# BARRAMENTO.net
KiCad netlist of a schematic drawn in Altium Designer
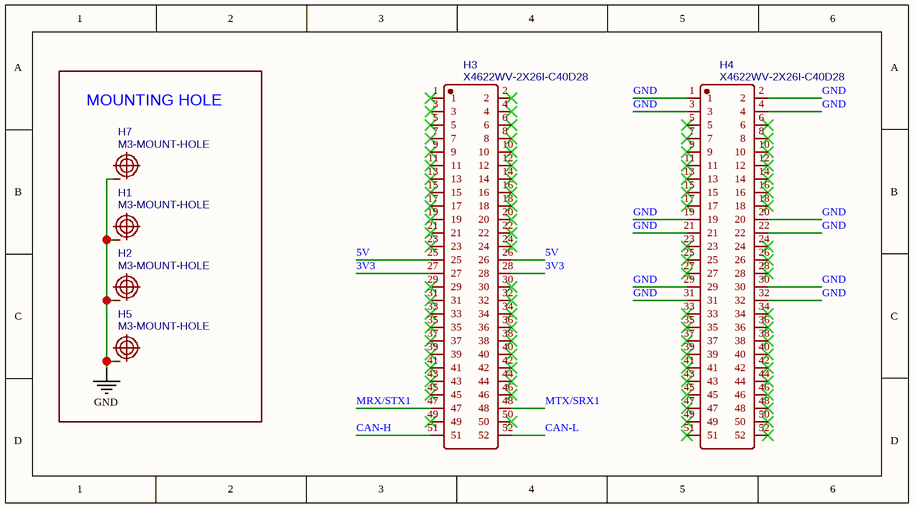
[diagram p0: BARRAMENTO.schdoc]

(export (version "E")
  (design (tool "Eeschema 10.0.6"))
  (components
    (comp (ref "H1")
      (value "M3-MOUNT-HOLE")
      (fields (field (name "CONTRIBUTOR") "amugona"))
      (libsource (lib "altium-import") (part "root_0_M3-MOUNT-HOLE_"))
    )
    (comp (ref "H2")
      (value "M3-MOUNT-HOLE")
      (fields (field (name "CONTRIBUTOR") "amugona"))
      (libsource (lib "altium-import") (part "root_0_M3-MOUNT-HOLE_"))
    )
    (comp (ref "H3")
      (value "X4622WV-2X26I-C40D28")
      (fields
        (field (name "BOM_SUPPLIER PART") "C2881769")
        (field (name "BOM_MANUFACTURER PART") "X1321FV-2x26-C43D24")
        (field (name "CONTRIBUTOR") "LCSC")
      )
      (libsource (lib "altium-import") (part "root_0_X4622WV-2X26I-C40D28_"))
    )
    (comp (ref "H4")
      (value "X4622WV-2X26I-C40D28")
      (fields
        (field (name "BOM_SUPPLIER PART") "C2881769")
        (field (name "BOM_MANUFACTURER PART") "X1321FV-2x26-C43D24")
        (field (name "CONTRIBUTOR") "LCSC")
      )
      (libsource (lib "altium-import") (part "root_0_X4622WV-2X26I-C40D28_"))
    )
    (comp (ref "H5")
      (value "M3-MOUNT-HOLE")
      (fields (field (name "CONTRIBUTOR") "amugona"))
      (libsource (lib "altium-import") (part "root_0_M3-MOUNT-HOLE_"))
    )
    (comp (ref "H7")
      (value "M3-MOUNT-HOLE")
      (fields (field (name "CONTRIBUTOR") "amugona"))
      (libsource (lib "altium-import") (part "root_0_M3-MOUNT-HOLE_"))
    )
  )
  (nets
    (net (code "1") (name "/3V3") (class "Default")
      (node (ref "H3") (pin "27") (pinfunction "27_27") (pintype "passive"))
      (node (ref "H3") (pin "28") (pinfunction "28_28") (pintype "passive"))
    )
    (net (code "2") (name "/5V") (class "Default")
      (node (ref "H3") (pin "25") (pinfunction "25_25") (pintype "passive"))
      (node (ref "H3") (pin "26") (pinfunction "26_26") (pintype "passive"))
    )
    (net (code "3") (name "/CAN-H") (class "Default")
      (node (ref "H3") (pin "51") (pinfunction "51_51") (pintype "passive"))
    )
    (net (code "4") (name "/CAN-L") (class "Default")
      (node (ref "H3") (pin "52") (pinfunction "52_52") (pintype "passive"))
    )
    (net (code "5") (name "/MRX{slash}STX1") (class "Default")
      (node (ref "H3") (pin "47") (pinfunction "47_47") (pintype "passive"))
    )
    (net (code "6") (name "/MTX{slash}SRX1") (class "Default")
      (node (ref "H3") (pin "48") (pinfunction "48_48") (pintype "passive"))
    )
    (net (code "7") (name "GND") (class "Default")
      (node (ref "H1") (pin "1") (pinfunction "1_1") (pintype "passive"))
      (node (ref "H2") (pin "1") (pinfunction "1_1") (pintype "passive"))
      (node (ref "H4") (pin "1") (pinfunction "1_1") (pintype "passive"))
      (node (ref "H4") (pin "19") (pinfunction "19_19") (pintype "passive"))
      (node (ref "H4") (pin "2") (pinfunction "2_2") (pintype "passive"))
      (node (ref "H4") (pin "20") (pinfunction "20_20") (pintype "passive"))
      (node (ref "H4") (pin "21") (pinfunction "21_21") (pintype "passive"))
      (node (ref "H4") (pin "22") (pinfunction "22_22") (pintype "passive"))
      (node (ref "H4") (pin "29") (pinfunction "29_29") (pintype "passive"))
      (node (ref "H4") (pin "3") (pinfunction "3_3") (pintype "passive"))
      (node (ref "H4") (pin "30") (pinfunction "30_30") (pintype "passive"))
      (node (ref "H4") (pin "31") (pinfunction "31_31") (pintype "passive"))
      (node (ref "H4") (pin "32") (pinfunction "32_32") (pintype "passive"))
      (node (ref "H4") (pin "4") (pinfunction "4_4") (pintype "passive"))
      (node (ref "H5") (pin "1") (pinfunction "1_1") (pintype "passive"))
      (node (ref "H7") (pin "1") (pinfunction "1_1") (pintype "passive"))
    )
    (net (code "8") (name "unconnected-(H3-Pad1)") (class "Default")
      (node (ref "H3") (pin "1") (pinfunction "1_1") (pintype "passive+no_connect"))
    )
    (net (code "9") (name "unconnected-(H3-Pad2)") (class "Default")
      (node (ref "H3") (pin "2") (pinfunction "2_2") (pintype "passive+no_connect"))
    )
    (net (code "10") (name "unconnected-(H3-Pad3)") (class "Default")
      (node (ref "H3") (pin "3") (pinfunction "3_3") (pintype "passive+no_connect"))
    )
    (net (code "11") (name "unconnected-(H3-Pad4)") (class "Default")
      (node (ref "H3") (pin "4") (pinfunction "4_4") (pintype "passive+no_connect"))
    )
    (net (code "12") (name "unconnected-(H3-Pad5)") (class "Default")
      (node (ref "H3") (pin "5") (pinfunction "5_5") (pintype "passive+no_connect"))
    )
    (net (code "13") (name "unconnected-(H3-Pad6)") (class "Default")
      (node (ref "H3") (pin "6") (pinfunction "6_6") (pintype "passive+no_connect"))
    )
    (net (code "14") (name "unconnected-(H3-Pad7)") (class "Default")
      (node (ref "H3") (pin "7") (pinfunction "7_7") (pintype "passive+no_connect"))
    )
    (net (code "15") (name "unconnected-(H3-Pad8)") (class "Default")
      (node (ref "H3") (pin "8") (pinfunction "8_8") (pintype "passive+no_connect"))
    )
    (net (code "16") (name "unconnected-(H3-Pad9)") (class "Default")
      (node (ref "H3") (pin "9") (pinfunction "9_9") (pintype "passive+no_connect"))
    )
    (net (code "17") (name "unconnected-(H3-Pad10)") (class "Default")
      (node (ref "H3") (pin "10") (pinfunction "10_10") (pintype "passive+no_connect"))
    )
    (net (code "18") (name "unconnected-(H3-Pad11)") (class "Default")
      (node (ref "H3") (pin "11") (pinfunction "11_11") (pintype "passive+no_connect"))
    )
    (net (code "19") (name "unconnected-(H3-Pad12)") (class "Default")
      (node (ref "H3") (pin "12") (pinfunction "12_12") (pintype "passive+no_connect"))
    )
    (net (code "20") (name "unconnected-(H3-Pad13)") (class "Default")
      (node (ref "H3") (pin "13") (pinfunction "13_13") (pintype "passive+no_connect"))
    )
    (net (code "21") (name "unconnected-(H3-Pad14)") (class "Default")
      (node (ref "H3") (pin "14") (pinfunction "14_14") (pintype "passive+no_connect"))
    )
    (net (code "22") (name "unconnected-(H3-Pad15)") (class "Default")
      (node (ref "H3") (pin "15") (pinfunction "15_15") (pintype "passive+no_connect"))
    )
    (net (code "23") (name "unconnected-(H3-Pad16)") (class "Default")
      (node (ref "H3") (pin "16") (pinfunction "16_16") (pintype "passive+no_connect"))
    )
    (net (code "24") (name "unconnected-(H3-Pad17)") (class "Default")
      (node (ref "H3") (pin "17") (pinfunction "17_17") (pintype "passive+no_connect"))
    )
    (net (code "25") (name "unconnected-(H3-Pad18)") (class "Default")
      (node (ref "H3") (pin "18") (pinfunction "18_18") (pintype "passive+no_connect"))
    )
    (net (code "26") (name "unconnected-(H3-Pad19)") (class "Default")
      (node (ref "H3") (pin "19") (pinfunction "19_19") (pintype "passive+no_connect"))
    )
    (net (code "27") (name "unconnected-(H3-Pad20)") (class "Default")
      (node (ref "H3") (pin "20") (pinfunction "20_20") (pintype "passive+no_connect"))
    )
    (net (code "28") (name "unconnected-(H3-Pad21)") (class "Default")
      (node (ref "H3") (pin "21") (pinfunction "21_21") (pintype "passive+no_connect"))
    )
    (net (code "29") (name "unconnected-(H3-Pad22)") (class "Default")
      (node (ref "H3") (pin "22") (pinfunction "22_22") (pintype "passive+no_connect"))
    )
    (net (code "30") (name "unconnected-(H3-Pad23)") (class "Default")
      (node (ref "H3") (pin "23") (pinfunction "23_23") (pintype "passive+no_connect"))
    )
    (net (code "31") (name "unconnected-(H3-Pad24)") (class "Default")
      (node (ref "H3") (pin "24") (pinfunction "24_24") (pintype "passive+no_connect"))
    )
    (net (code "32") (name "unconnected-(H3-Pad29)") (class "Default")
      (node (ref "H3") (pin "29") (pinfunction "29_29") (pintype "passive+no_connect"))
    )
    (net (code "33") (name "unconnected-(H3-Pad30)") (class "Default")
      (node (ref "H3") (pin "30") (pinfunction "30_30") (pintype "passive+no_connect"))
    )
    (net (code "34") (name "unconnected-(H3-Pad31)") (class "Default")
      (node (ref "H3") (pin "31") (pinfunction "31_31") (pintype "passive+no_connect"))
    )
    (net (code "35") (name "unconnected-(H3-Pad32)") (class "Default")
      (node (ref "H3") (pin "32") (pinfunction "32_32") (pintype "passive+no_connect"))
    )
    (net (code "36") (name "unconnected-(H3-Pad33)") (class "Default")
      (node (ref "H3") (pin "33") (pinfunction "33_33") (pintype "passive+no_connect"))
    )
    (net (code "37") (name "unconnected-(H3-Pad34)") (class "Default")
      (node (ref "H3") (pin "34") (pinfunction "34_34") (pintype "passive+no_connect"))
    )
    (net (code "38") (name "unconnected-(H3-Pad35)") (class "Default")
      (node (ref "H3") (pin "35") (pinfunction "35_35") (pintype "passive+no_connect"))
    )
    (net (code "39") (name "unconnected-(H3-Pad36)") (class "Default")
      (node (ref "H3") (pin "36") (pinfunction "36_36") (pintype "passive+no_connect"))
    )
    (net (code "40") (name "unconnected-(H3-Pad37)") (class "Default")
      (node (ref "H3") (pin "37") (pinfunction "37_37") (pintype "passive+no_connect"))
    )
    (net (code "41") (name "unconnected-(H3-Pad38)") (class "Default")
      (node (ref "H3") (pin "38") (pinfunction "38_38") (pintype "passive+no_connect"))
    )
    (net (code "42") (name "unconnected-(H3-Pad39)") (class "Default")
      (node (ref "H3") (pin "39") (pinfunction "39_39") (pintype "passive+no_connect"))
    )
    (net (code "43") (name "unconnected-(H3-Pad40)") (class "Default")
      (node (ref "H3") (pin "40") (pinfunction "40_40") (pintype "passive+no_connect"))
    )
    (net (code "44") (name "unconnected-(H3-Pad41)") (class "Default")
      (node (ref "H3") (pin "41") (pinfunction "41_41") (pintype "passive+no_connect"))
    )
    (net (code "45") (name "unconnected-(H3-Pad42)") (class "Default")
      (node (ref "H3") (pin "42") (pinfunction "42_42") (pintype "passive+no_connect"))
    )
    (net (code "46") (name "unconnected-(H3-Pad43)") (class "Default")
      (node (ref "H3") (pin "43") (pinfunction "43_43") (pintype "passive+no_connect"))
    )
    (net (code "47") (name "unconnected-(H3-Pad44)") (class "Default")
      (node (ref "H3") (pin "44") (pinfunction "44_44") (pintype "passive+no_connect"))
    )
    (net (code "48") (name "unconnected-(H3-Pad45)") (class "Default")
      (node (ref "H3") (pin "45") (pinfunction "45_45") (pintype "passive+no_connect"))
    )
    (net (code "49") (name "unconnected-(H3-Pad46)") (class "Default")
      (node (ref "H3") (pin "46") (pinfunction "46_46") (pintype "passive+no_connect"))
    )
    (net (code "50") (name "unconnected-(H3-Pad49)") (class "Default")
      (node (ref "H3") (pin "49") (pinfunction "49_49") (pintype "passive+no_connect"))
    )
    (net (code "51") (name "unconnected-(H3-Pad50)") (class "Default")
      (node (ref "H3") (pin "50") (pinfunction "50_50") (pintype "passive+no_connect"))
    )
    (net (code "52") (name "unconnected-(H4-Pad5)") (class "Default")
      (node (ref "H4") (pin "5") (pinfunction "5_5") (pintype "passive+no_connect"))
    )
    (net (code "53") (name "unconnected-(H4-Pad6)") (class "Default")
      (node (ref "H4") (pin "6") (pinfunction "6_6") (pintype "passive+no_connect"))
    )
    (net (code "54") (name "unconnected-(H4-Pad7)") (class "Default")
      (node (ref "H4") (pin "7") (pinfunction "7_7") (pintype "passive+no_connect"))
    )
    (net (code "55") (name "unconnected-(H4-Pad8)") (class "Default")
      (node (ref "H4") (pin "8") (pinfunction "8_8") (pintype "passive+no_connect"))
    )
    (net (code "56") (name "unconnected-(H4-Pad9)") (class "Default")
      (node (ref "H4") (pin "9") (pinfunction "9_9") (pintype "passive+no_connect"))
    )
    (net (code "57") (name "unconnected-(H4-Pad10)") (class "Default")
      (node (ref "H4") (pin "10") (pinfunction "10_10") (pintype "passive+no_connect"))
    )
    (net (code "58") (name "unconnected-(H4-Pad11)") (class "Default")
      (node (ref "H4") (pin "11") (pinfunction "11_11") (pintype "passive+no_connect"))
    )
    (net (code "59") (name "unconnected-(H4-Pad12)") (class "Default")
      (node (ref "H4") (pin "12") (pinfunction "12_12") (pintype "passive+no_connect"))
    )
    (net (code "60") (name "unconnected-(H4-Pad13)") (class "Default")
      (node (ref "H4") (pin "13") (pinfunction "13_13") (pintype "passive+no_connect"))
    )
    (net (code "61") (name "unconnected-(H4-Pad14)") (class "Default")
      (node (ref "H4") (pin "14") (pinfunction "14_14") (pintype "passive+no_connect"))
    )
    (net (code "62") (name "unconnected-(H4-Pad15)") (class "Default")
      (node (ref "H4") (pin "15") (pinfunction "15_15") (pintype "passive+no_connect"))
    )
    (net (code "63") (name "unconnected-(H4-Pad16)") (class "Default")
      (node (ref "H4") (pin "16") (pinfunction "16_16") (pintype "passive+no_connect"))
    )
    (net (code "64") (name "unconnected-(H4-Pad17)") (class "Default")
      (node (ref "H4") (pin "17") (pinfunction "17_17") (pintype "passive+no_connect"))
    )
    (net (code "65") (name "unconnected-(H4-Pad18)") (class "Default")
      (node (ref "H4") (pin "18") (pinfunction "18_18") (pintype "passive+no_connect"))
    )
    (net (code "66") (name "unconnected-(H4-Pad23)") (class "Default")
      (node (ref "H4") (pin "23") (pinfunction "23_23") (pintype "passive+no_connect"))
    )
    (net (code "67") (name "unconnected-(H4-Pad24)") (class "Default")
      (node (ref "H4") (pin "24") (pinfunction "24_24") (pintype "passive+no_connect"))
    )
    (net (code "68") (name "unconnected-(H4-Pad25)") (class "Default")
      (node (ref "H4") (pin "25") (pinfunction "25_25") (pintype "passive+no_connect"))
    )
    (net (code "69") (name "unconnected-(H4-Pad26)") (class "Default")
      (node (ref "H4") (pin "26") (pinfunction "26_26") (pintype "passive+no_connect"))
    )
    (net (code "70") (name "unconnected-(H4-Pad27)") (class "Default")
      (node (ref "H4") (pin "27") (pinfunction "27_27") (pintype "passive+no_connect"))
    )
    (net (code "71") (name "unconnected-(H4-Pad28)") (class "Default")
      (node (ref "H4") (pin "28") (pinfunction "28_28") (pintype "passive+no_connect"))
    )
    (net (code "72") (name "unconnected-(H4-Pad33)") (class "Default")
      (node (ref "H4") (pin "33") (pinfunction "33_33") (pintype "passive+no_connect"))
    )
    (net (code "73") (name "unconnected-(H4-Pad34)") (class "Default")
      (node (ref "H4") (pin "34") (pinfunction "34_34") (pintype "passive+no_connect"))
    )
    (net (code "74") (name "unconnected-(H4-Pad35)") (class "Default")
      (node (ref "H4") (pin "35") (pinfunction "35_35") (pintype "passive+no_connect"))
    )
    (net (code "75") (name "unconnected-(H4-Pad36)") (class "Default")
      (node (ref "H4") (pin "36") (pinfunction "36_36") (pintype "passive+no_connect"))
    )
    (net (code "76") (name "unconnected-(H4-Pad37)") (class "Default")
      (node (ref "H4") (pin "37") (pinfunction "37_37") (pintype "passive+no_connect"))
    )
    (net (code "77") (name "unconnected-(H4-Pad38)") (class "Default")
      (node (ref "H4") (pin "38") (pinfunction "38_38") (pintype "passive+no_connect"))
    )
    (net (code "78") (name "unconnected-(H4-Pad39)") (class "Default")
      (node (ref "H4") (pin "39") (pinfunction "39_39") (pintype "passive+no_connect"))
    )
    (net (code "79") (name "unconnected-(H4-Pad40)") (class "Default")
      (node (ref "H4") (pin "40") (pinfunction "40_40") (pintype "passive+no_connect"))
    )
    (net (code "80") (name "unconnected-(H4-Pad41)") (class "Default")
      (node (ref "H4") (pin "41") (pinfunction "41_41") (pintype "passive+no_connect"))
    )
    (net (code "81") (name "unconnected-(H4-Pad42)") (class "Default")
      (node (ref "H4") (pin "42") (pinfunction "42_42") (pintype "passive+no_connect"))
    )
    (net (code "82") (name "unconnected-(H4-Pad43)") (class "Default")
      (node (ref "H4") (pin "43") (pinfunction "43_43") (pintype "passive+no_connect"))
    )
    (net (code "83") (name "unconnected-(H4-Pad44)") (class "Default")
      (node (ref "H4") (pin "44") (pinfunction "44_44") (pintype "passive+no_connect"))
    )
    (net (code "84") (name "unconnected-(H4-Pad45)") (class "Default")
      (node (ref "H4") (pin "45") (pinfunction "45_45") (pintype "passive+no_connect"))
    )
    (net (code "85") (name "unconnected-(H4-Pad46)") (class "Default")
      (node (ref "H4") (pin "46") (pinfunction "46_46") (pintype "passive+no_connect"))
    )
    (net (code "86") (name "unconnected-(H4-Pad47)") (class "Default")
      (node (ref "H4") (pin "47") (pinfunction "47_47") (pintype "passive+no_connect"))
    )
    (net (code "87") (name "unconnected-(H4-Pad48)") (class "Default")
      (node (ref "H4") (pin "48") (pinfunction "48_48") (pintype "passive+no_connect"))
    )
    (net (code "88") (name "unconnected-(H4-Pad49)") (class "Default")
      (node (ref "H4") (pin "49") (pinfunction "49_49") (pintype "passive+no_connect"))
    )
    (net (code "89") (name "unconnected-(H4-Pad50)") (class "Default")
      (node (ref "H4") (pin "50") (pinfunction "50_50") (pintype "passive+no_connect"))
    )
    (net (code "90") (name "unconnected-(H4-Pad51)") (class "Default")
      (node (ref "H4") (pin "51") (pinfunction "51_51") (pintype "passive+no_connect"))
    )
    (net (code "91") (name "unconnected-(H4-Pad52)") (class "Default")
      (node (ref "H4") (pin "52") (pinfunction "52_52") (pintype "passive+no_connect"))
    )
  )
)
